# ReboostV2__Vsense.net
KiCad netlist of a schematic drawn in Altium Designer
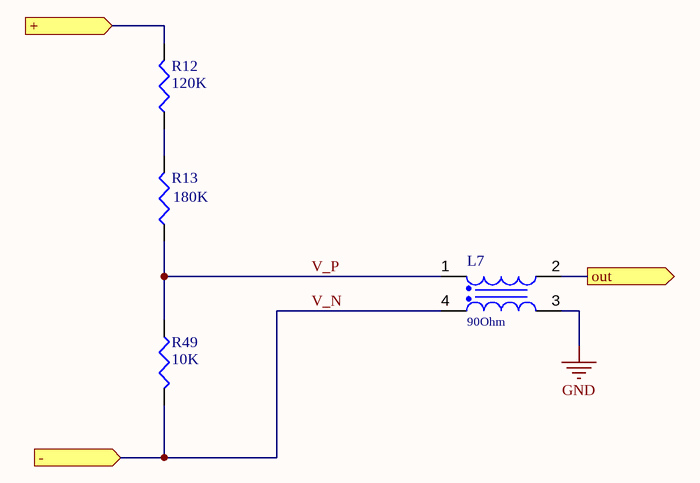
[diagram p0: ReboostV2__Vsense.SchDoc]

(export (version "E")
  (design (tool "Eeschema 10.0.6"))
  (components
    (comp (ref "L7")
      (value "90Ohm")
      (footprint "WE-CNSW_0805")
      (description "WE-CNSW SMT Common Mode Line Filter, size 0805, 90Ohm, 0.37A, 50V")
      (fields
        (field (name "MANUFACTURER PART NUMBER") "744231091")
        (field (name "MANUFACTURER") "Wurth Elektronik")
      )
      (libsource (lib "WE-CNSW (rev20a)") (part "744231091"))
    )
    (comp (ref "R12")
      (value "120K")
      (footprint "0603")
      (description "Resistor, 120K, 1%, 0.063W, 50V, 100PPM, 0603")
      (libsource (lib "AR_Resistors_SMD") (part "120K/0603/0063W/50V"))
    )
    (comp (ref "R13")
      (value "180K")
      (footprint "0603")
      (description "Resistor, 180K, 1%, 0.063W, 50V, 100PPM, 0603")
      (libsource (lib "AR_Resistors_SMD") (part "180K/0603/0063W/50V"))
    )
    (comp (ref "R49")
      (value "10K")
      (footprint "0603")
      (description "Resistor, 10K, 1%, 0.063W, 50V, 100PPM, 0603")
      (libsource (lib "AR_Resistors_SMD") (part "10K/0603/0063W/50V"))
    )
  )
  (nets
    (net (code "1") (name "/+") (class "Default")
      (node (ref "R12") (pin "2") (pinfunction "2_2") (pintype "passive"))
    )
    (net (code "2") (name "/V_N") (class "Default")
      (node (ref "L7") (pin "4") (pinfunction "4_4") (pintype "passive"))
      (node (ref "R49") (pin "2") (pinfunction "2_2") (pintype "passive"))
    )
    (net (code "3") (name "/V_P") (class "Default")
      (node (ref "L7") (pin "1") (pinfunction "1_1") (pintype "passive"))
      (node (ref "R13") (pin "1") (pinfunction "1_1") (pintype "passive"))
      (node (ref "R49") (pin "1") (pinfunction "1_1") (pintype "passive"))
    )
    (net (code "4") (name "/out") (class "Default")
      (node (ref "L7") (pin "2") (pinfunction "2_2") (pintype "passive"))
    )
    (net (code "5") (name "GND") (class "Default")
      (node (ref "L7") (pin "3") (pinfunction "3_3") (pintype "passive"))
    )
    (net (code "6") (name "Net-(R12-Pad1)") (class "Default")
      (node (ref "R12") (pin "1") (pinfunction "1_1") (pintype "passive"))
      (node (ref "R13") (pin "2") (pinfunction "2_2") (pintype "passive"))
    )
  )
)
